# Artemis-Nano.net
KiCad netlist of a schematic drawn in EAGLE
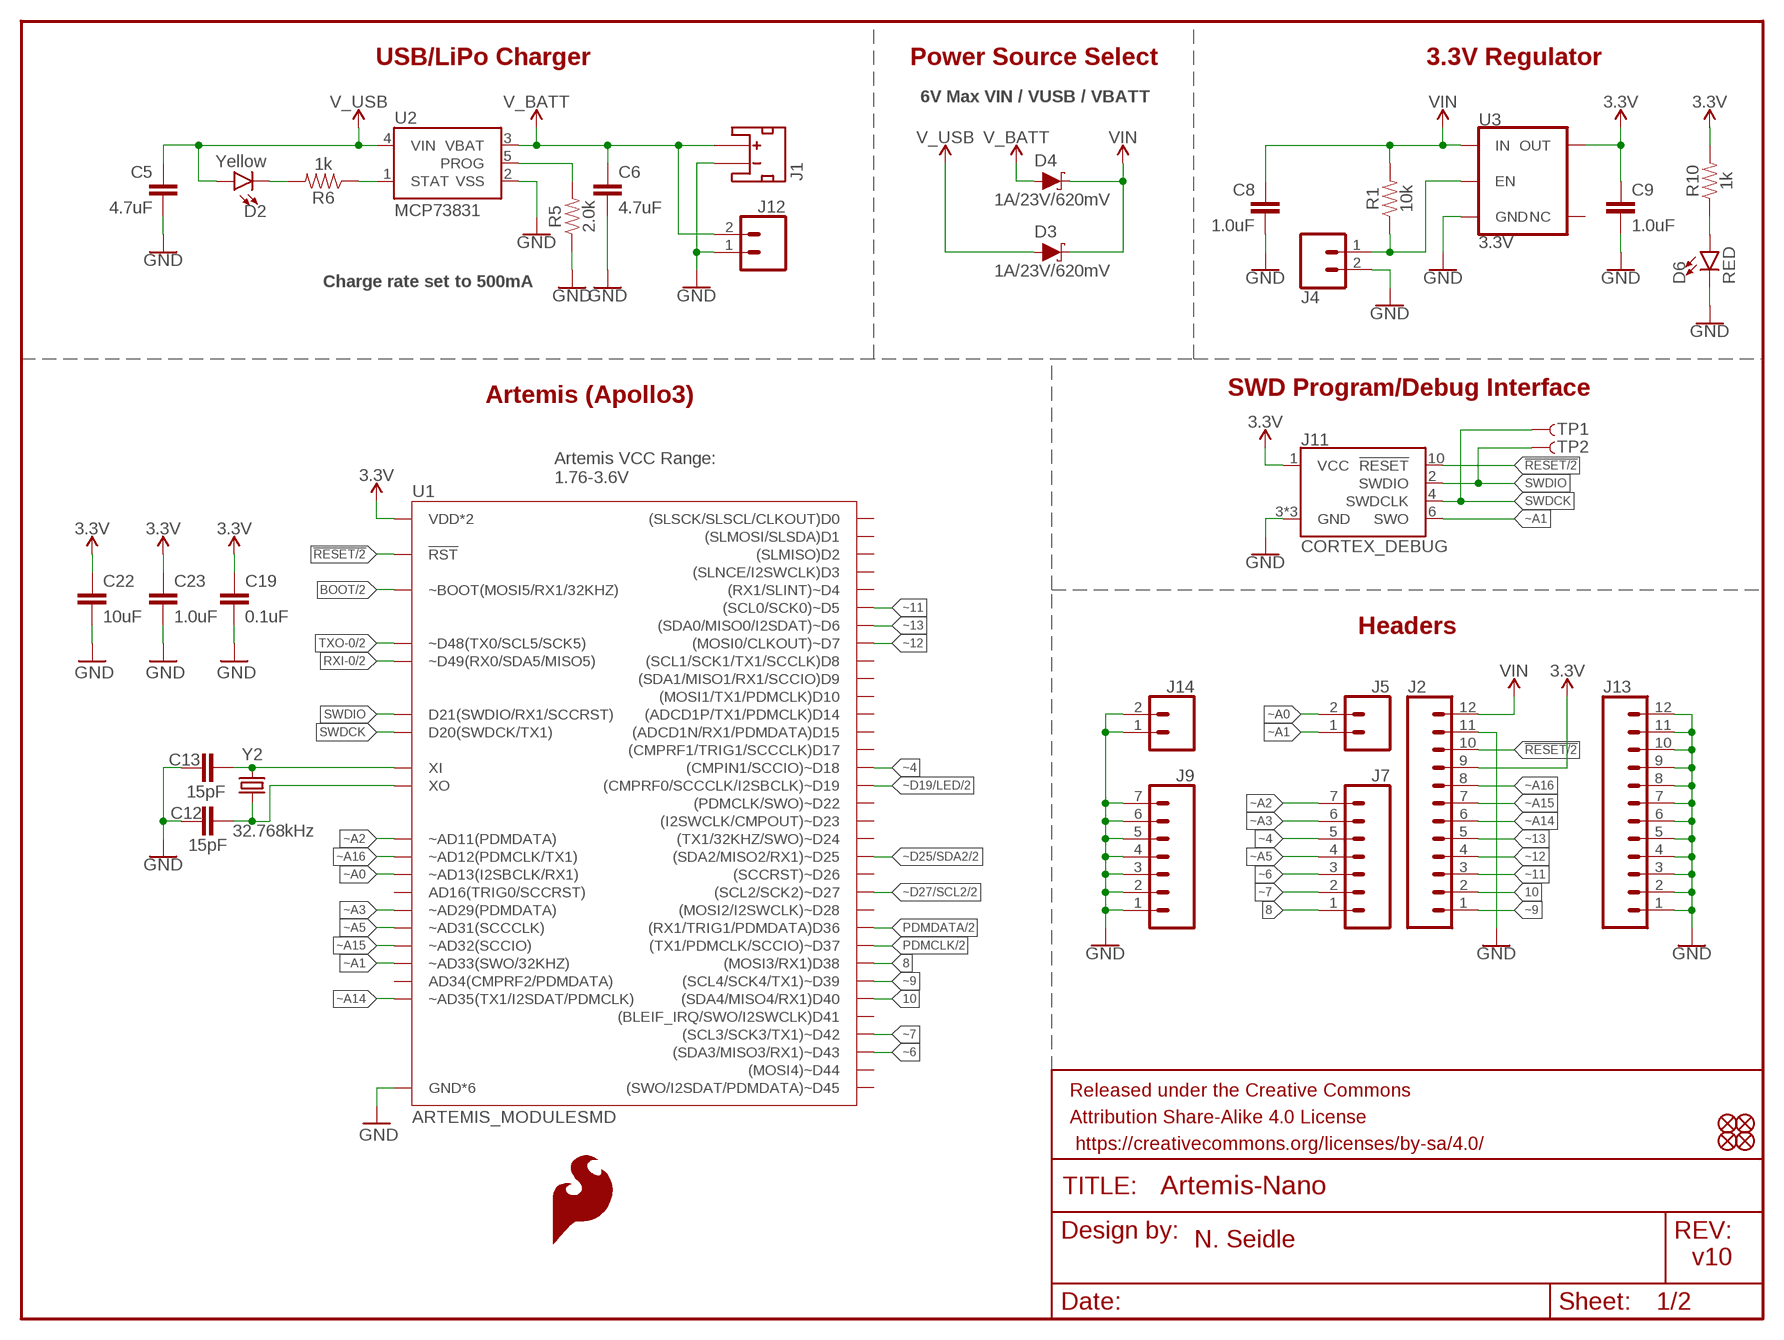
[diagram p0: schematic, sheet 1]
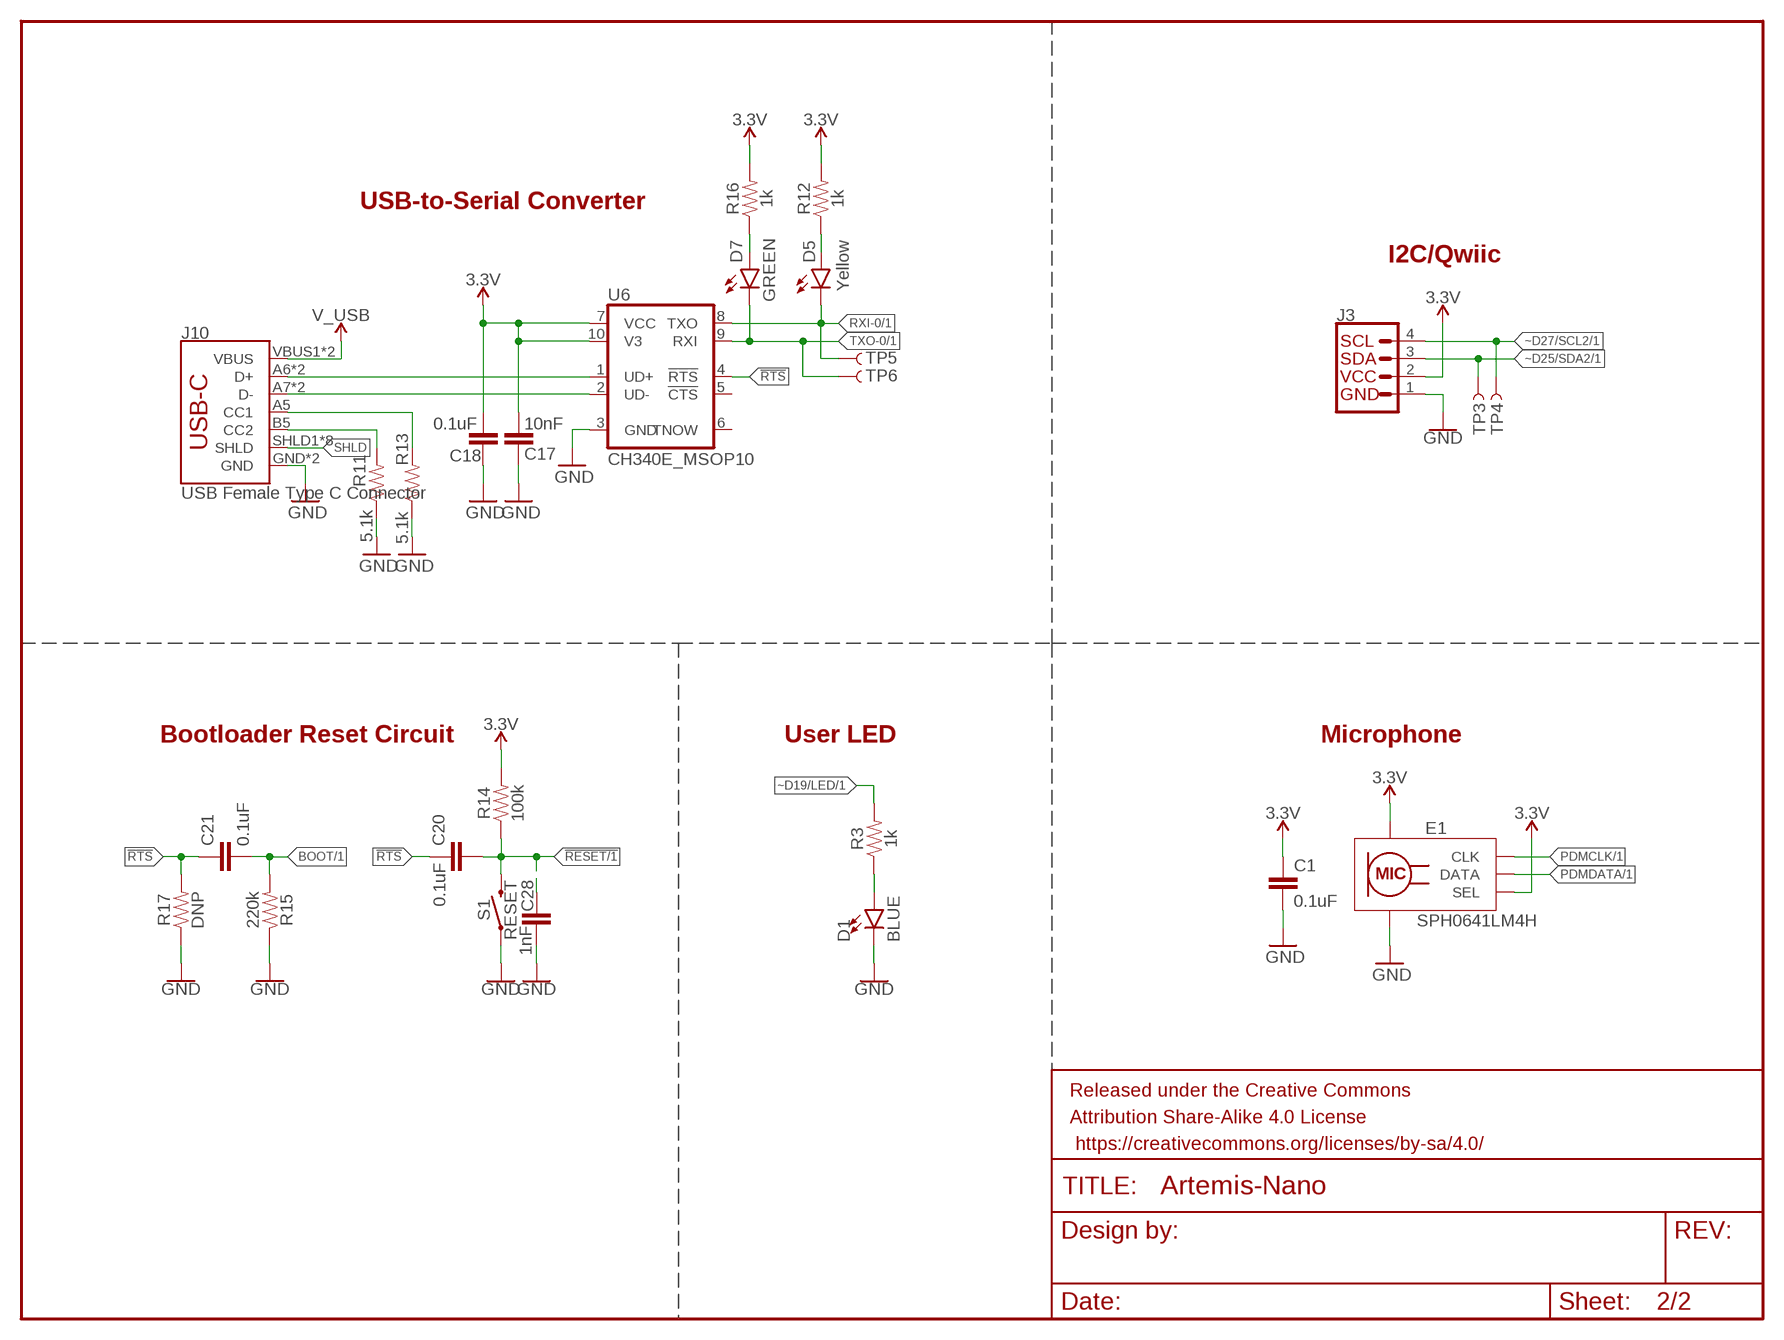
[diagram p1: schematic, sheet 2]

(export (version "E")
  (design (tool "Eeschema 10.0.6"))
  (components
    (comp (ref "C5")
      (value "4.7uF")
      (footprint "eagle-import:0603")
      (libsource (lib "eagle-import") (part "4.7UF-0603-6.3V-(10%)"))
    )
    (comp (ref "C6")
      (value "4.7uF")
      (footprint "eagle-import:0603")
      (libsource (lib "eagle-import") (part "4.7UF-0603-6.3V-(10%)"))
    )
    (comp (ref "C8")
      (value "1.0uF")
      (footprint "eagle-import:0402-TIGHT")
      (libsource (lib "eagle-import") (part "1.0UF-0402T-16V-10%"))
    )
    (comp (ref "C9")
      (value "1.0uF")
      (footprint "eagle-import:0402-TIGHT")
      (libsource (lib "eagle-import") (part "1.0UF-0402T-16V-10%"))
    )
    (comp (ref "C12")
      (value "15pF")
      (footprint "eagle-import:0603")
      (libsource (lib "eagle-import") (part "15PF-0603-50V-5%"))
    )
    (comp (ref "C13")
      (value "15pF")
      (footprint "eagle-import:0603")
      (libsource (lib "eagle-import") (part "15PF-0603-50V-5%"))
    )
    (comp (ref "C19")
      (value "0.1uF")
      (footprint "eagle-import:0402-TIGHT")
      (libsource (lib "eagle-import") (part "0.1UF-0402T-16V-10%"))
    )
    (comp (ref "C22")
      (value "10uF")
      (footprint "eagle-import:0603")
      (libsource (lib "eagle-import") (part "10UF-0603-6.3V-20%"))
    )
    (comp (ref "C23")
      (value "1.0uF")
      (footprint "eagle-import:0402-TIGHT")
      (libsource (lib "eagle-import") (part "1.0UF-0402T-16V-10%"))
    )
    (comp (ref "D2")
      (value "Yellow")
      (footprint "eagle-import:LED-0603")
      (libsource (lib "eagle-import") (part "LED-YELLOW0603"))
    )
    (comp (ref "D3")
      (value "1A/23V/620mV")
      (footprint "eagle-import:SOD-323")
      (libsource (lib "eagle-import") (part "DIODE-SCHOTTKY-BAT20J"))
    )
    (comp (ref "D4")
      (value "1A/23V/620mV")
      (footprint "eagle-import:SOD-323")
      (libsource (lib "eagle-import") (part "DIODE-SCHOTTKY-BAT20J"))
    )
    (comp (ref "D6")
      (value "RED")
      (footprint "eagle-import:LED-0603")
      (libsource (lib "eagle-import") (part "LED-RED0603"))
    )
    (comp (ref "FD1")
      (value "FIDUCIALUFIDUCIAL")
      (footprint "eagle-import:FIDUCIAL-MICRO")
      (libsource (lib "eagle-import") (part "FIDUCIALUFIDUCIAL"))
    )
    (comp (ref "FD2")
      (value "FIDUCIALUFIDUCIAL")
      (footprint "eagle-import:FIDUCIAL-MICRO")
      (libsource (lib "eagle-import") (part "FIDUCIALUFIDUCIAL"))
    )
    (comp (ref "FD3")
      (value "FIDUCIALUFIDUCIAL")
      (footprint "eagle-import:FIDUCIAL-MICRO")
      (libsource (lib "eagle-import") (part "FIDUCIALUFIDUCIAL"))
    )
    (comp (ref "FD4")
      (value "FIDUCIALUFIDUCIAL")
      (footprint "eagle-import:FIDUCIAL-MICRO")
      (libsource (lib "eagle-import") (part "FIDUCIALUFIDUCIAL"))
    )
    (comp (ref "FRAME1")
      (value "FRAME-LETTER")
      (footprint "eagle-import:CREATIVE_COMMONS")
      (libsource (lib "eagle-import") (part "FRAME-LETTER"))
    )
    (comp (ref "J1")
      (value "JST_2MM_MALE")
      (footprint "eagle-import:JST-2-SMD")
      (libsource (lib "eagle-import") (part "JST_2MM_MALE"))
    )
    (comp (ref "J2")
      (value "CONN_12NO_SILK")
      (footprint "eagle-import:1X12_NO_SILK")
      (libsource (lib "eagle-import") (part "CONN_12NO_SILK"))
    )
    (comp (ref "J4")
      (value "CONN_021X02_NO_SILK")
      (footprint "eagle-import:1X02_NO_SILK")
      (libsource (lib "eagle-import") (part "CONN_021X02_NO_SILK"))
    )
    (comp (ref "J5")
      (value "CONN_021X02_NO_SILK")
      (footprint "eagle-import:1X02_NO_SILK")
      (libsource (lib "eagle-import") (part "CONN_021X02_NO_SILK"))
    )
    (comp (ref "J7")
      (value "CONN_07NO_SILK")
      (footprint "eagle-import:1X07_NO_SILK")
      (libsource (lib "eagle-import") (part "CONN_07NO_SILK"))
    )
    (comp (ref "J9")
      (value "CONN_07NO_SILK")
      (footprint "eagle-import:1X07_NO_SILK")
      (libsource (lib "eagle-import") (part "CONN_07NO_SILK"))
    )
    (comp (ref "J11")
      (value "CORTEX_DEBUG")
      (footprint "eagle-import:2X5-PTH-1.27MM-NO_SILK")
      (libsource (lib "eagle-import") (part "CORTEX_DEBUG_MINIMUM_PTH_NS"))
    )
    (comp (ref "J12")
      (value "CONN_021X02_NO_SILK")
      (footprint "eagle-import:1X02_NO_SILK")
      (libsource (lib "eagle-import") (part "CONN_021X02_NO_SILK"))
    )
    (comp (ref "J13")
      (value "CONN_12NO_SILK")
      (footprint "eagle-import:1X12_NO_SILK")
      (libsource (lib "eagle-import") (part "CONN_12NO_SILK"))
    )
    (comp (ref "J14")
      (value "CONN_021X02_NO_SILK")
      (footprint "eagle-import:1X02_NO_SILK")
      (libsource (lib "eagle-import") (part "CONN_021X02_NO_SILK"))
    )
    (comp (ref "LOGO1")
      (value "SFE_LOGO_FLAME.1_INCH")
      (footprint "eagle-import:SFE_LOGO_FLAME_.1")
      (libsource (lib "eagle-import") (part "SFE_LOGO_FLAME.1_INCH"))
    )
    (comp (ref "LOGO4")
      (value "SFE_LOGO_FLAME.1_INCH")
      (footprint "eagle-import:SFE_LOGO_FLAME_.1")
      (libsource (lib "eagle-import") (part "SFE_LOGO_FLAME.1_INCH"))
    )
    (comp (ref "R1")
      (value "10k")
      (footprint "eagle-import:0603")
      (libsource (lib "eagle-import") (part "10KOHM-0603-1/10W-1%"))
    )
    (comp (ref "R5")
      (value "2.0k")
      (footprint "eagle-import:0603")
      (libsource (lib "eagle-import") (part "2.0KOHM-0603-1/10W-5%"))
    )
    (comp (ref "R6")
      (value "1k")
      (footprint "eagle-import:0603")
      (libsource (lib "eagle-import") (part "1KOHM-0603-1/10W-1%"))
    )
    (comp (ref "R10")
      (value "1k")
      (footprint "eagle-import:0603")
      (libsource (lib "eagle-import") (part "1KOHM-0603-1/10W-1%"))
    )
    (comp (ref "TP1")
      (value "TEST-POINT3X5")
      (footprint "eagle-import:PAD.03X.05")
      (libsource (lib "eagle-import") (part "TEST-POINT3X5"))
    )
    (comp (ref "TP2")
      (value "TEST-POINT3X5")
      (footprint "eagle-import:PAD.03X.05")
      (libsource (lib "eagle-import") (part "TEST-POINT3X5"))
    )
    (comp (ref "U1")
      (value "ARTEMIS_MODULESMD")
      (footprint "eagle-import:ARTEMIS_FP")
      (libsource (lib "eagle-import") (part "ARTEMIS_MODULESMD"))
    )
    (comp (ref "U2")
      (value "MCP73831")
      (footprint "eagle-import:SOT23-5")
      (libsource (lib "eagle-import") (part "MCP73831"))
    )
    (comp (ref "U3")
      (value "3.3V")
      (footprint "eagle-import:SOT23-5")
      (libsource (lib "eagle-import") (part "V_REG_AP2112K-3.3V"))
    )
    (comp (ref "Y2")
      (value "32.768kHz")
      (footprint "eagle-import:CRYSTAL-SMD-3.2X1.5MM")
      (libsource (lib "eagle-import") (part "CRYSTAL-32.768KHZSMD-3.2X1.5"))
    )
    (comp (ref "C1")
      (value "0.1uF")
      (footprint "eagle-import:0402-TIGHT")
      (libsource (lib "eagle-import") (part "0.1UF-0402T-16V-10%"))
    )
    (comp (ref "C17")
      (value "10nF")
      (footprint "eagle-import:0603")
      (libsource (lib "eagle-import") (part "10NF-0603-50V-10%"))
    )
    (comp (ref "C18")
      (value "0.1uF")
      (footprint "eagle-import:0603")
      (libsource (lib "eagle-import") (part "0.1UF-0603-25V-(+80/-20%)"))
    )
    (comp (ref "C20")
      (value "0.1uF")
      (footprint "eagle-import:0603")
      (libsource (lib "eagle-import") (part "0.1UF-0603-25V-5%"))
    )
    (comp (ref "C21")
      (value "0.1uF")
      (footprint "eagle-import:0603")
      (libsource (lib "eagle-import") (part "0.1UF-0603-25V-5%"))
    )
    (comp (ref "C28")
      (value "1nF")
      (footprint "eagle-import:0603")
      (libsource (lib "eagle-import") (part "1.0NF/1000PF-0603-50V-10%"))
    )
    (comp (ref "D1")
      (value "BLUE")
      (footprint "eagle-import:LED-0603")
      (libsource (lib "eagle-import") (part "LED-BLUE0603"))
    )
    (comp (ref "D5")
      (value "Yellow")
      (footprint "eagle-import:LED-0603")
      (libsource (lib "eagle-import") (part "LED-YELLOW0603"))
    )
    (comp (ref "D7")
      (value "GREEN")
      (footprint "eagle-import:LED-0603")
      (libsource (lib "eagle-import") (part "LED-GREEN0603"))
    )
    (comp (ref "E1")
      (value "SPH0641LM4H")
      (footprint "eagle-import:SPH0641LM4H-1_MICROPHONE")
      (libsource (lib "eagle-import") (part "SPH0641LM4H-1_MICROPHONE"))
    )
    (comp (ref "FRAME2")
      (value "FRAME-LETTERNO_PACKAGE")
      (footprint "eagle-import:DUMMY")
      (fields (field (name "DESIGNER") "Nobody"))
      (libsource (lib "eagle-import") (part "FRAME-LETTERNO_PACKAGE"))
    )
    (comp (ref "J3")
      (value "QWIIC_CONNECTORJS-1MM")
      (footprint "eagle-import:JST04_1MM_RA")
      (libsource (lib "eagle-import") (part "QWIIC_CONNECTORJS-1MM"))
    )
    (comp (ref "J10")
      (value "USB Female Type C Connector")
      (footprint "eagle-import:USB-C-16P-4LAYER-ISOLATED")
      (libsource (lib "eagle-import") (part "USB_C4-LAYER-ISOLATED"))
    )
    (comp (ref "R3")
      (value "1k")
      (footprint "eagle-import:0603")
      (libsource (lib "eagle-import") (part "1KOHM-0603-1/10W-1%"))
    )
    (comp (ref "R11")
      (value "5.1k")
      (footprint "eagle-import:0603")
      (libsource (lib "eagle-import") (part "5.1KOHM5.1KOHM-0603-1/10W-1%"))
    )
    (comp (ref "R12")
      (value "1k")
      (footprint "eagle-import:0603")
      (libsource (lib "eagle-import") (part "1KOHM-0603-1/10W-1%"))
    )
    (comp (ref "R13")
      (value "5.1k")
      (footprint "eagle-import:0603")
      (libsource (lib "eagle-import") (part "5.1KOHM5.1KOHM-0603-1/10W-1%"))
    )
    (comp (ref "R14")
      (value "100k")
      (footprint "eagle-import:0603")
      (libsource (lib "eagle-import") (part "100KOHM-0603-1/10W-1%"))
    )
    (comp (ref "R15")
      (value "220k")
      (footprint "eagle-import:0603")
      (libsource (lib "eagle-import") (part "220KOHM-0603-1/10W-1%"))
    )
    (comp (ref "R16")
      (value "1k")
      (footprint "eagle-import:0603")
      (libsource (lib "eagle-import") (part "1KOHM-0603-1/10W-1%"))
    )
    (comp (ref "R17")
      (value "DNP")
      (footprint "eagle-import:0603")
      (libsource (lib "eagle-import") (part "RESISTOR0603"))
    )
    (comp (ref "S1")
      (value "RESET")
      (footprint "eagle-import:TACTILE_SWITCH_SMD_4.6X2.8MM")
      (libsource (lib "eagle-import") (part "MOMENTARY-SWITCH-SPST-SMD-4.6X2.8MM"))
    )
    (comp (ref "TP3")
      (value "TEST-POINT3X5")
      (footprint "eagle-import:PAD.03X.05")
      (libsource (lib "eagle-import") (part "TEST-POINT3X5"))
    )
    (comp (ref "TP4")
      (value "TEST-POINT3X5")
      (footprint "eagle-import:PAD.03X.05")
      (libsource (lib "eagle-import") (part "TEST-POINT3X5"))
    )
    (comp (ref "TP5")
      (value "TEST-POINT3X5")
      (footprint "eagle-import:PAD.03X.05")
      (libsource (lib "eagle-import") (part "TEST-POINT3X5"))
    )
    (comp (ref "TP6")
      (value "TEST-POINT3X5")
      (footprint "eagle-import:PAD.03X.05")
      (libsource (lib "eagle-import") (part "TEST-POINT3X5"))
    )
    (comp (ref "U6")
      (value "CH340E_MSOP10")
      (footprint "eagle-import:MSOP10")
      (libsource (lib "eagle-import") (part "CH340E_MSOP10"))
    )
  )
  (nets
    (net (code "1") (name "3.3V") (class "Default")
      (node (ref "C1") (pin "1") (pinfunction "1_1") (pintype "passive"))
      (node (ref "C17") (pin "1") (pinfunction "1_1") (pintype "passive"))
      (node (ref "C18") (pin "1") (pinfunction "1_1") (pintype "passive"))
      (node (ref "C19") (pin "2") (pinfunction "2_2") (pintype "passive"))
      (node (ref "C22") (pin "1") (pinfunction "1_1") (pintype "passive"))
      (node (ref "C23") (pin "1") (pinfunction "1_1") (pintype "passive"))
      (node (ref "C9") (pin "1") (pinfunction "1_1") (pintype "passive"))
      (node (ref "E1") (pin "2") (pinfunction "SEL_2") (pintype "input"))
      (node (ref "E1") (pin "5") (pinfunction "VDD_5") (pintype "power_in"))
      (node (ref "J11") (pin "1") (pinfunction "VCC_1") (pintype "bidirectional"))
      (node (ref "J2") (pin "9") (pinfunction "9_9") (pintype "passive"))
      (node (ref "J3") (pin "2") (pinfunction "2_2") (pintype "power_in"))
      (node (ref "R10") (pin "2") (pinfunction "2_2") (pintype "passive"))
      (node (ref "R12") (pin "2") (pinfunction "2_2") (pintype "passive"))
      (node (ref "R14") (pin "2") (pinfunction "2_2") (pintype "passive"))
      (node (ref "R16") (pin "2") (pinfunction "2_2") (pintype "passive"))
      (node (ref "U1") (pin "VDD@36") (pinfunction "VDD*2_VDD@36") (pintype "bidirectional"))
      (node (ref "U1") (pin "VDD@37") (pinfunction "VDD*2_VDD@37") (pintype "bidirectional"))
      (node (ref "U3") (pin "5") (pinfunction "OUT_5") (pintype "passive"))
      (node (ref "U6") (pin "10") (pinfunction "V3_10") (pintype "bidirectional"))
      (node (ref "U6") (pin "7") (pinfunction "VCC_7") (pintype "bidirectional"))
    )
    (net (code "2") (name "8") (class "Default")
      (node (ref "J7") (pin "1") (pinfunction "1_1") (pintype "passive"))
      (node (ref "U1") (pin "D38") (pinfunction "(MOSI3/RX1)D38_D38") (pintype "bidirectional"))
    )
    (net (code "3") (name "10") (class "Default")
      (node (ref "J2") (pin "2") (pinfunction "2_2") (pintype "passive"))
      (node (ref "U1") (pin "D40") (pinfunction "(SDA4/MISO4/RX1)D40_D40") (pintype "bidirectional"))
    )
    (net (code "4") (name "BOOT") (class "Default")
      (node (ref "C21") (pin "2") (pinfunction "2_2") (pintype "passive"))
      (node (ref "R15") (pin "2") (pinfunction "2_2") (pintype "passive"))
      (node (ref "U1") (pin "BOOT") (pinfunction "~{BOOT(MOSI5/RX1/32KHZ})_BOOT") (pintype "bidirectional"))
    )
    (net (code "5") (name "GND") (class "Default")
      (node (ref "C1") (pin "2") (pinfunction "2_2") (pintype "passive"))
      (node (ref "C12") (pin "1") (pinfunction "1_1") (pintype "passive"))
      (node (ref "C13") (pin "1") (pinfunction "1_1") (pintype "passive"))
      (node (ref "C17") (pin "2") (pinfunction "2_2") (pintype "passive"))
      (node (ref "C18") (pin "2") (pinfunction "2_2") (pintype "passive"))
      (node (ref "C19") (pin "1") (pinfunction "1_1") (pintype "passive"))
      (node (ref "C22") (pin "2") (pinfunction "2_2") (pintype "passive"))
      (node (ref "C23") (pin "2") (pinfunction "2_2") (pintype "passive"))
      (node (ref "C28") (pin "2") (pinfunction "2_2") (pintype "passive"))
      (node (ref "C5") (pin "2") (pinfunction "2_2") (pintype "passive"))
      (node (ref "C6") (pin "2") (pinfunction "2_2") (pintype "passive"))
      (node (ref "C8") (pin "2") (pinfunction "2_2") (pintype "passive"))
      (node (ref "C9") (pin "2") (pinfunction "2_2") (pintype "passive"))
      (node (ref "D1") (pin "C") (pinfunction "C_C") (pintype "passive"))
      (node (ref "D6") (pin "C") (pinfunction "C_C") (pintype "passive"))
      (node (ref "E1") (pin "3") (pinfunction "GND_3") (pintype "power_in"))
      (node (ref "E1") (pin "6") (pinfunction "GND_6") (pintype "power_in"))
      (node (ref "E1") (pin "7") (pinfunction "GND_7") (pintype "power_in"))
      (node (ref "E1") (pin "8") (pinfunction "GND_8") (pintype "power_in"))
      (node (ref "J1") (pin "1") (pinfunction "-_1") (pintype "bidirectional"))
      (node (ref "J10") (pin "GND") (pinfunction "GND_GND") (pintype "bidirectional"))
      (node (ref "J10") (pin "GND2") (pinfunction "GND_GND2") (pintype "bidirectional"))
      (node (ref "J11") (pin "3") (pinfunction "GND_3") (pintype "bidirectional"))
      (node (ref "J11") (pin "5") (pinfunction "GND_5") (pintype "bidirectional"))
      (node (ref "J11") (pin "9") (pinfunction "GND_9") (pintype "bidirectional"))
      (node (ref "J12") (pin "1") (pinfunction "1_1") (pintype "passive"))
      (node (ref "J13") (pin "1") (pinfunction "1_1") (pintype "passive"))
      (node (ref "J13") (pin "10") (pinfunction "10_10") (pintype "passive"))
      (node (ref "J13") (pin "11") (pinfunction "11_11") (pintype "passive"))
      (node (ref "J13") (pin "12") (pinfunction "12_12") (pintype "passive"))
      (node (ref "J13") (pin "2") (pinfunction "2_2") (pintype "passive"))
      (node (ref "J13") (pin "3") (pinfunction "3_3") (pintype "passive"))
      (node (ref "J13") (pin "4") (pinfunction "4_4") (pintype "passive"))
      (node (ref "J13") (pin "5") (pinfunction "5_5") (pintype "passive"))
      (node (ref "J13") (pin "6") (pinfunction "6_6") (pintype "passive"))
      (node (ref "J13") (pin "7") (pinfunction "7_7") (pintype "passive"))
      (node (ref "J13") (pin "8") (pinfunction "8_8") (pintype "passive"))
      (node (ref "J13") (pin "9") (pinfunction "9_9") (pintype "passive"))
      (node (ref "J14") (pin "1") (pinfunction "1_1") (pintype "passive"))
      (node (ref "J14") (pin "2") (pinfunction "2_2") (pintype "passive"))
      (node (ref "J2") (pin "11") (pinfunction "11_11") (pintype "passive"))
      (node (ref "J3") (pin "1") (pinfunction "1_1") (pintype "power_in"))
      (node (ref "J4") (pin "2") (pinfunction "2_2") (pintype "passive"))
      (node (ref "J9") (pin "1") (pinfunction "1_1") (pintype "passive"))
      (node (ref "J9") (pin "2") (pinfunction "2_2") (pintype "passive"))
      (node (ref "J9") (pin "3") (pinfunction "3_3") (pintype "passive"))
      (node (ref "J9") (pin "4") (pinfunction "4_4") (pintype "passive"))
      (node (ref "J9") (pin "5") (pinfunction "5_5") (pintype "passive"))
      (node (ref "J9") (pin "6") (pinfunction "6_6") (pintype "passive"))
      (node (ref "J9") (pin "7") (pinfunction "7_7") (pintype "passive"))
      (node (ref "R11") (pin "1") (pinfunction "1_1") (pintype "passive"))
      (node (ref "R13") (pin "1") (pinfunction "1_1") (pintype "passive"))
      (node (ref "R15") (pin "1") (pinfunction "1_1") (pintype "passive"))
      (node (ref "R17") (pin "1") (pinfunction "1_1") (pintype "passive"))
      (node (ref "R5") (pin "1") (pinfunction "1_1") (pintype "passive"))
      (node (ref "S1") (pin "1") (pinfunction "1_1") (pintype "passive"))
      (node (ref "S1") (pin "2") (pinfunction "1_2") (pintype "passive"))
      (node (ref "U1") (pin "GND@1") (pinfunction "GND*6_GND@1") (pintype "bidirectional"))
      (node (ref "U1") (pin "GND@22") (pinfunction "GND*6_GND@22") (pintype "bidirectional"))
      (node (ref "U1") (pin "GND@38") (pinfunction "GND*6_GND@38") (pintype "bidirectional"))
      (node (ref "U1") (pin "GND@39") (pinfunction "GND*6_GND@39") (pintype "bidirectional"))
      (node (ref "U1") (pin "GND@47") (pinfunction "GND*6_GND@47") (pintype "bidirectional"))
      (node (ref "U1") (pin "GND@59") (pinfunction "GND*6_GND@59") (pintype "bidirectional"))
      (node (ref "U2") (pin "2") (pinfunction "VSS_2") (pintype "power_in"))
      (node (ref "U3") (pin "2") (pinfunction "GND_2") (pintype "input"))
      (node (ref "U6") (pin "3") (pinfunction "GND_3") (pintype "bidirectional"))
    )
    (net (code "6") (name "Net-(D1-PadA)") (class "Default")
      (node (ref "D1") (pin "A") (pinfunction "A_A") (pintype "passive"))
      (node (ref "R3") (pin "1") (pinfunction "1_1") (pintype "passive"))
    )
    (net (code "7") (name "Net-(D2-PadC)") (class "Default")
      (node (ref "D2") (pin "C") (pinfunction "C_C") (pintype "passive"))
      (node (ref "R6") (pin "2") (pinfunction "2_2") (pintype "passive"))
    )
    (net (code "8") (name "Net-(D5-PadA)") (class "Default")
      (node (ref "D5") (pin "A") (pinfunction "A_A") (pintype "passive"))
      (node (ref "R12") (pin "1") (pinfunction "1_1") (pintype "passive"))
    )
    (net (code "9") (name "Net-(D6-PadA)") (class "Default")
      (node (ref "D6") (pin "A") (pinfunction "A_A") (pintype "passive"))
      (node (ref "R10") (pin "1") (pinfunction "1_1") (pintype "passive"))
    )
    (net (code "10") (name "Net-(D7-PadA)") (class "Default")
      (node (ref "D7") (pin "A") (pinfunction "A_A") (pintype "passive"))
      (node (ref "R16") (pin "1") (pinfunction "1_1") (pintype "passive"))
    )
    (net (code "11") (name "Net-(J10-CC1)") (class "Default")
      (node (ref "J10") (pin "A5") (pinfunction "CC1_A5") (pintype "bidirectional"))
      (node (ref "R13") (pin "2") (pinfunction "2_2") (pintype "passive"))
    )
    (net (code "12") (name "Net-(J10-CC2)") (class "Default")
      (node (ref "J10") (pin "B5") (pinfunction "CC2_B5") (pintype "bidirectional"))
      (node (ref "R11") (pin "2") (pinfunction "2_2") (pintype "passive"))
    )
    (net (code "13") (name "Net-(U2-PROG)") (class "Default")
      (node (ref "R5") (pin "2") (pinfunction "2_2") (pintype "passive"))
      (node (ref "U2") (pin "5") (pinfunction "PROG_5") (pintype "input"))
    )
    (net (code "14") (name "Net-(U2-STAT)") (class "Default")
      (node (ref "R6") (pin "1") (pinfunction "1_1") (pintype "passive"))
      (node (ref "U2") (pin "1") (pinfunction "STAT_1") (pintype "output"))
    )
    (net (code "15") (name "Net-(U3-EN)") (class "Default")
      (node (ref "J4") (pin "1") (pinfunction "1_1") (pintype "passive"))
      (node (ref "R1") (pin "1") (pinfunction "1_1") (pintype "passive"))
      (node (ref "U3") (pin "3") (pinfunction "EN_3") (pintype "input"))
    )
    (net (code "16") (name "Net-(U6-UD+)") (class "Default")
      (node (ref "J10") (pin "A6") (pinfunction "D+_A6") (pintype "bidirectional"))
      (node (ref "J10") (pin "B6") (pinfunction "D+_B6") (pintype "bidirectional"))
      (node (ref "U6") (pin "1") (pinfunction "UD+_1") (pintype "bidirectional"))
    )
    (net (code "17") (name "Net-(U6-UD-)") (class "Default")
      (node (ref "J10") (pin "A7") (pinfunction "D-_A7") (pintype "bidirectional"))
      (node (ref "J10") (pin "B7") (pinfunction "D-_B7") (pintype "bidirectional"))
      (node (ref "U6") (pin "2") (pinfunction "UD-_2") (pintype "bidirectional"))
    )
    (net (code "18") (name "Net-(Y2-1)") (class "Default")
      (node (ref "C13") (pin "2") (pinfunction "2_2") (pintype "passive"))
      (node (ref "U1") (pin "XI") (pinfunction "XI_XI") (pintype "bidirectional"))
      (node (ref "Y2") (pin "P$1") (pinfunction "1_P$1") (pintype "passive"))
    )
    (net (code "19") (name "Net-(Y2-2)") (class "Default")
      (node (ref "C12") (pin "2") (pinfunction "2_2") (pintype "passive"))
      (node (ref "U1") (pin "XO") (pinfunction "XO_XO") (pintype "bidirectional"))
      (node (ref "Y2") (pin "P$2") (pinfunction "2_P$2") (pintype "passive"))
    )
    (net (code "20") (name "PDMCLK") (class "Default")
      (node (ref "E1") (pin "4") (pinfunction "CLK_4") (pintype "input"))
      (node (ref "U1") (pin "~D37") (pinfunction "(TX1/PDMCLK/SCCIO)~{D37}_~D37") (pintype "bidirectional"))
    )
    (net (code "21") (name "PDMDATA") (class "Default")
      (node (ref "E1") (pin "1") (pinfunction "DATA_1") (pintype "output"))
      (node (ref "U1") (pin "D36") (pinfunction "(RX1/TRIG1/PDMDATA)D36_D36") (pintype "bidirectional"))
    )
    (net (code "22") (name "RXI-0") (class "Default")
      (node (ref "D5") (pin "C") (pinfunction "C_C") (pintype "passive"))
      (node (ref "TP5") (pin "P$1") (pinfunction "1_P$1") (pintype "bidirectional"))
      (node (ref "U1") (pin "RXI-0") (pinfunction "~{D49(RX0/SDA5/MISO5})_RXI-0") (pintype "bidirectional"))
      (node (ref "U6") (pin "8") (pinfunction "TXO_8") (pintype "bidirectional"))
    )
    (net (code "23") (name "SHLD") (class "Default")
      (node (ref "J10") (pin "SHLD1") (pinfunction "SHLD_SHLD1") (pintype "bidirectional"))
      (node (ref "J10") (pin "SHLD2") (pinfunction "SHLD_SHLD2") (pintype "bidirectional"))
      (node (ref "J10") (pin "SHLD3") (pinfunction "SHLD_SHLD3") (pintype "bidirectional"))
      (node (ref "J10") (pin "SHLD4") (pinfunction "SHLD_SHLD4") (pintype "bidirectional"))
      (node (ref "J10") (pin "SHLD5") (pinfunction "SHLD_SHLD5") (pintype "bidirectional"))
      (node (ref "J10") (pin "SHLD6") (pinfunction "SHLD_SHLD6") (pintype "bidirectional"))
      (node (ref "J10") (pin "SHLD7") (pinfunction "SHLD_SHLD7") (pintype "bidirectional"))
      (node (ref "J10") (pin "SHLD8") (pinfunction "SHLD_SHLD8") (pintype "bidirectional"))
    )
    (net (code "24") (name "SWDCK") (class "Default")
      (node (ref "J11") (pin "4") (pinfunction "SWDCLK_4") (pintype "bidirectional"))
      (node (ref "TP1") (pin "P$1") (pinfunction "1_P$1") (pintype "bidirectional"))
      (node (ref "U1") (pin "SWDCK") (pinfunction "D20(SWDCK/TX1)_SWDCK") (pintype "bidirectional"))
    )
    (net (code "25") (name "SWDIO") (class "Default")
      (node (ref "J11") (pin "2") (pinfunction "SWDIO_2") (pintype "bidirectional"))
      (node (ref "TP2") (pin "P$1") (pinfunction "1_P$1") (pintype "bidirectional"))
      (node (ref "U1") (pin "SWDIO") (pinfunction "D21(SWDIO/RX1/SCCRST)_SWDIO") (pintype "bidirectional"))
    )
    (net (code "26") (name "TXO-0") (class "Default")
      (node (ref "D7") (pin "C") (pinfunction "C_C") (pintype "passive"))
      (node (ref "TP6") (pin "P$1") (pinfunction "1_P$1") (pintype "bidirectional"))
      (node (ref "U1") (pin "TXO-0") (pinfunction "~{D48(TX0/SCL5/SCK5})_TXO-0") (pintype "bidirectional"))
      (node (ref "U6") (pin "9") (pinfunction "RXI_9") (pintype "bidirectional"))
    )
    (net (code "27") (name "VIN") (class "Default")
      (node (ref "C8") (pin "1") (pinfunction "1_1") (pintype "passive"))
      (node (ref "D3") (pin "C") (pinfunction "C_C") (pintype "passive"))
      (node (ref "D4") (pin "C") (pinfunction "C_C") (pintype "passive"))
      (node (ref "J2") (pin "12") (pinfunction "12_12") (pintype "passive"))
      (node (ref "R1") (pin "2") (pinfunction "2_2") (pintype "passive"))
      (node (ref "U3") (pin "1") (pinfunction "IN_1") (pintype "input"))
    )
    (net (code "28") (name "V_BATT") (class "Default")
      (node (ref "C6") (pin "1") (pinfunction "1_1") (pintype "passive"))
      (node (ref "D4") (pin "A") (pinfunction "A_A") (pintype "passive"))
      (node (ref "J1") (pin "2") (pinfunction "+_2") (pintype "bidirectional"))
      (node (ref "J12") (pin "2") (pinfunction "2_2") (pintype "passive"))
      (node (ref "U2") (pin "3") (pinfunction "VBAT_3") (pintype "power_in"))
    )
    (net (code "29") (name "V_USB") (class "Default")
      (node (ref "C5") (pin "1") (pinfunction "1_1") (pintype "passive"))
      (node (ref "D2") (pin "A") (pinfunction "A_A") (pintype "passive"))
      (node (ref "D3") (pin "A") (pinfunction "A_A") (pintype "passive"))
      (node (ref "J10") (pin "VBUS1") (pinfunction "VBUS_VBUS1") (pintype "bidirectional"))
      (node (ref "J10") (pin "VBUS2") (pinfunction "VBUS_VBUS2") (pintype "bidirectional"))
      (node (ref "U2") (pin "4") (pinfunction "VIN_4") (pintype "power_in"))
    )
    (net (code "30") (name "unconnected-(J1-PAD1-PadNC1)") (class "Default")
      (node (ref "J1") (pin "NC1") (pinfunction "PAD1_NC1") (pintype "bidirectional"))
    )
    (net (code "31") (name "unconnected-(J1-PAD2-PadNC2)") (class "Default")
      (node (ref "J1") (pin "NC2") (pinfunction "PAD2_NC2") (pintype "bidirectional"))
    )
    (net (code "32") (name "unconnected-(U1-(ADCD1N{slash}RX1{slash}PDMDATA)D15-PadD15)") (class "Default")
      (node (ref "U1") (pin "D15") (pinfunction "(ADCD1N/RX1/PDMDATA)D15_D15") (pintype "bidirectional"))
    )
    (net (code "33") (name "unconnected-(U1-(ADCD1P{slash}TX1{slash}PDMCLK)D14-PadD14)") (class "Default")
      (node (ref "U1") (pin "D14") (pinfunction "(ADCD1P/TX1/PDMCLK)D14_D14") (pintype "bidirectional"))
    )
    (net (code "34") (name "unconnected-(U1-(BLEIF_IRQ{slash}SWO{slash}I2SWCLK)D41-PadD41)") (class "Default")
      (node (ref "U1") (pin "D41") (pinfunction "(BLEIF_IRQ/SWO/I2SWCLK)D41_D41") (pintype "bidirectional"))
    )
    (net (code "35") (name "unconnected-(U1-(CMPRF1{slash}TRIG1{slash}SCCCLK)D17-PadD17)") (class "Default")
      (node (ref "U1") (pin "D17") (pinfunction "(CMPRF1/TRIG1/SCCCLK)D17_D17") (pintype "bidirectional"))
    )
    (net (code "36") (name "unconnected-(U1-(I2SWCLK{slash}CMPOUT)~{D23}-Pad~D23)") (class "Default")
      (node (ref "U1") (pin "~D23") (pinfunction "(I2SWCLK/CMPOUT)~{D23}_~D23") (pintype "bidirectional"))
    )
    (net (code "37") (name "unconnected-(U1-(MOSI1{slash}TX1{slash}PDMCLK)D10-PadD10)") (class "Default")
      (node (ref "U1") (pin "D10") (pinfunction "(MOSI1/TX1/PDMCLK)D10_D10") (pintype "bidirectional"))
    )
    (net (code "38") (name "unconnected-(U1-(MOSI2{slash}I2SWCLK)~{D28}-Pad~D28)") (class "Default")
      (node (ref "U1") (pin "~D28") (pinfunction "(MOSI2/I2SWCLK)~{D28}_~D28") (pintype "bidirectional"))
    )
    (net (code "39") (name "unconnected-(U1-(MOSI4)~{D44}-Pad~D44)") (class "Default")
      (node (ref "U1") (pin "~D44") (pinfunction "(MOSI4)~{D44}_~D44") (pintype "bidirectional"))
    )
    (net (code "40") (name "unconnected-(U1-(PDMCLK{slash}SWO)~{D22}-Pad~D22)") (class "Default")
      (node (ref "U1") (pin "~D22") (pinfunction "(PDMCLK/SWO)~{D22}_~D22") (pintype "bidirectional"))
    )
    (net (code "41") (name "unconnected-(U1-(RX1{slash}SLINT)~{D4}-Pad~D4)") (class "Default")
      (node (ref "U1") (pin "~D4") (pinfunction "(RX1/SLINT)~{D4}_~D4") (pintype "bidirectional"))
    )
    (net (code "42") (name "unconnected-(U1-(SCCRST)~{D26}-Pad~D26)") (class "Default")
      (node (ref "U1") (pin "~D26") (pinfunction "(SCCRST)~{D26}_~D26") (pintype "bidirectional"))
    )
    (net (code "43") (name "unconnected-(U1-(SCL1{slash}SCK1{slash}TX1{slash}SCCLK)D8-PadD8)") (class "Default")
      (node (ref "U1") (pin "D8") (pinfunction "(SCL1/SCK1/TX1/SCCLK)D8_D8") (pintype "bidirectional"))
    )
    (net (code "44") (name "unconnected-(U1-(SDA1{slash}MISO1{slash}RX1{slash}SCCIO)D9-PadD9)") (class "Default")
      (node (ref "U1") (pin "D9") (pinfunction "(SDA1/MISO1/RX1/SCCIO)D9_D9") (pintype "bidirectional"))
    )
    (net (code "45") (name "unconnected-(U1-(SLMISO)D2-PadD2)") (class "Default")
      (node (ref "U1") (pin "D2") (pinfunction "(SLMISO)D2_D2") (pintype "bidirectional"))
    )
    (net (code "46") (name "unconnected-(U1-(SLMOSI{slash}SLSDA)D1-PadD1)") (class "Default")
      (node (ref "U1") (pin "D1") (pinfunction "(SLMOSI/SLSDA)D1_D1") (pintype "bidirectional"))
    )
    (net (code "47") (name "unconnected-(U1-(SLNCE{slash}I2SWCLK)D3-PadD3)") (class "Default")
      (node (ref "U1") (pin "D3") (pinfunction "(SLNCE/I2SWCLK)D3_D3") (pintype "bidirectional"))
    )
    (net (code "48") (name "unconnected-(U1-(SLSCK{slash}SLSCL{slash}CLKOUT)D0-PadD0)") (class "Default")
      (node (ref "U1") (pin "D0") (pinfunction "(SLSCK/SLSCL/CLKOUT)D0_D0") (pintype "bidirectional"))
    )
    (net (code "49") (name "unconnected-(U1-(SWO{slash}I2SDAT{slash}PDMDATA)~{D45}-Pad~D45)") (class "Default")
      (node (ref "U1") (pin "~D45") (pinfunction "(SWO/I2SDAT/PDMDATA)~{D45}_~D45") (pintype "bidirectional"))
    )
    (net (code "50") (name "unconnected-(U1-(TX1{slash}32KHZ{slash}SWO)~{D24}-Pad~D24)") (class "Default")
      (node (ref "U1") (pin "~D24") (pinfunction "(TX1/32KHZ/SWO)~{D24}_~D24") (pintype "bidirectional"))
    )
    (net (code "51") (name "unconnected-(U1-AD16(TRIG0{slash}SCCRST)-PadAD16)") (class "Default")
      (node (ref "U1") (pin "AD16") (pinfunction "AD16(TRIG0/SCCRST)_AD16") (pintype "bidirectional"))
    )
    (net (code "52") (name "unconnected-(U1-AD34(CMPRF2{slash}PDMDATA)-PadAD34)") (class "Default")
      (node (ref "U1") (pin "AD34") (pinfunction "AD34(CMPRF2/PDMDATA)_AD34") (pintype "bidirectional"))
    )
    (net (code "53") (name "unconnected-(U3-NC-Pad4)") (class "Default")
      (node (ref "U3") (pin "4") (pinfunction "NC_4") (pintype "no_connect"))
    )
    (net (code "54") (name "unconnected-(U6-TNOW-Pad6)") (class "Default")
      (node (ref "U6") (pin "6") (pinfunction "TNOW_6") (pintype "bidirectional"))
    )
    (net (code "55") (name "unconnected-(U6-~{CTS}-Pad5)") (class "Default")
      (node (ref "U6") (pin "5") (pinfunction "~{CTS}_5") (pintype "bidirectional"))
    )
    (net (code "56") (name "~{4}") (class "Default")
      (node (ref "J7") (pin "5") (pinfunction "5_5") (pintype "passive"))
      (node (ref "U1") (pin "~D18") (pinfunction "(CMPIN1/SCCIO)~{D18}_~D18") (pintype "bidirectional"))
    )
    (net (code "57") (name "~{6}") (class "Default")
      (node (ref "J7") (pin "3") (pinfunction "3_3") (pintype "passive"))
      (node (ref "U1") (pin "~D43") (pinfunction "(SDA3/MISO3/RX1)~{D43}_~D43") (pintype "bidirectional"))
    )
    (net (code "58") (name "~{7}") (class "Default")
      (node (ref "J7") (pin "2") (pinfunction "2_2") (pintype "passive"))
      (node (ref "U1") (pin "~D42") (pinfunction "(SCL3/SCK3/TX1)~{D42}_~D42") (pintype "bidirectional"))
    )
    (net (code "59") (name "~{9}") (class "Default")
      (node (ref "J2") (pin "1") (pinfunction "1_1") (pintype "passive"))
      (node (ref "U1") (pin "~D39") (pinfunction "(SCL4/SCK4/TX1)~{D39}_~D39") (pintype "bidirectional"))
    )
    (net (code "60") (name "~{11}") (class "Default")
      (node (ref "J2") (pin "3") (pinfunction "3_3") (pintype "passive"))
      (node (ref "U1") (pin "~D5") (pinfunction "(SCL0/SCK0)~{D5}_~D5") (pintype "bidirectional"))
    )
    (net (code "61") (name "~{12}") (class "Default")
      (node (ref "J2") (pin "4") (pinfunction "4_4") (pintype "passive"))
      (node (ref "U1") (pin "D7") (pinfunction "(MOSI0/CLKOUT)~{D7}_D7") (pintype "bidirectional"))
    )
    (net (code "62") (name "~{13}") (class "Default")
      (node (ref "J2") (pin "5") (pinfunction "5_5") (pintype "passive"))
      (node (ref "U1") (pin "~D6") (pinfunction "(SDA0/MISO0/I2SDAT)~{D6}_~D6") (pintype "bidirectional"))
    )
    (net (code "63") (name "~{A0}") (class "Default")
      (node (ref "J5") (pin "2") (pinfunction "2_2") (pintype "passive"))
      (node (ref "U1") (pin "~AD13") (pinfunction "~{AD13(I2SBCLK/RX1})_~AD13") (pintype "bidirectional"))
    )
    (net (code "64") (name "~{A1}") (class "Default")
      (node (ref "J11") (pin "6") (pinfunction "SWO_6") (pintype "bidirectional"))
      (node (ref "J5") (pin "1") (pinfunction "1_1") (pintype "passive"))
      (node (ref "U1") (pin "~AD33/SWO") (pinfunction "~{AD33(SWO/32KHZ})_~AD33/SWO") (pintype "bidirectional"))
    )
    (net (code "65") (name "~{A2}") (class "Default")
      (node (ref "J7") (pin "7") (pinfunction "7_7") (pintype "passive"))
      (node (ref "U1") (pin "~AD11") (pinfunction "~{AD11(PDMDATA})_~AD11") (pintype "bidirectional"))
    )
    (net (code "66") (name "~{A3}") (class "Default")
      (node (ref "J7") (pin "6") (pinfunction "6_6") (pintype "passive"))
      (node (ref "U1") (pin "~AD29") (pinfunction "~{AD29(PDMDATA})_~AD29") (pintype "bidirectional"))
    )
    (net (code "67") (name "~{A5}") (class "Default")
      (node (ref "J7") (pin "4") (pinfunction "4_4") (pintype "passive"))
      (node (ref "U1") (pin "~AD31") (pinfunction "~{AD31(SCCCLK})_~AD31") (pintype "bidirectional"))
    )
    (net (code "68") (name "~{A14}") (class "Default")
      (node (ref "J2") (pin "6") (pinfunction "6_6") (pintype "passive"))
      (node (ref "U1") (pin "~AD35") (pinfunction "~{AD35(TX1/I2SDAT/PDMCLK})_~AD35") (pintype "bidirectional"))
    )
    (net (code "69") (name "~{A15}") (class "Default")
      (node (ref "J2") (pin "7") (pinfunction "7_7") (pintype "passive"))
      (node (ref "U1") (pin "~AD32") (pinfunction "~{AD32(SCCIO})_~AD32") (pintype "bidirectional"))
    )
    (net (code "70") (name "~{A16}") (class "Default")
      (node (ref "J2") (pin "8") (pinfunction "8_8") (pintype "passive"))
      (node (ref "U1") (pin "~AD12") (pinfunction "~{AD12(PDMCLK/TX1})_~AD12") (pintype "bidirectional"))
    )
    (net (code "71") (name "~{D19{slash}LED}") (class "Default")
      (node (ref "R3") (pin "2") (pinfunction "2_2") (pintype "passive"))
      (node (ref "U1") (pin "~D19") (pinfunction "(CMPRF0/SCCCLK/I2SBCLK)~{D19}_~D19") (pintype "bidirectional"))
    )
    (net (code "72") (name "~{D25{slash}SDA2}") (class "Default")
      (node (ref "J3") (pin "3") (pinfunction "3_3") (pintype "passive"))
      (node (ref "TP3") (pin "P$1") (pinfunction "1_P$1") (pintype "bidirectional"))
      (node (ref "U1") (pin "~D25") (pinfunction "(SDA2/MISO2/RX1)~{D25}_~D25") (pintype "bidirectional"))
    )
    (net (code "73") (name "~{D27{slash}SCL2}") (class "Default")
      (node (ref "J3") (pin "4") (pinfunction "4_4") (pintype "passive"))
      (node (ref "TP4") (pin "P$1") (pinfunction "1_P$1") (pintype "bidirectional"))
      (node (ref "U1") (pin "~D27") (pinfunction "(SCL2/SCK2)~{D27}_~D27") (pintype "bidirectional"))
    )
    (net (code "74") (name "~{RESET}") (class "Default")
      (node (ref "C20") (pin "2") (pinfunction "2_2") (pintype "passive"))
      (node (ref "C28") (pin "1") (pinfunction "1_1") (pintype "passive"))
      (node (ref "J11") (pin "10") (pinfunction "~{RESET}_10") (pintype "bidirectional"))
      (node (ref "J2") (pin "10") (pinfunction "10_10") (pintype "passive"))
      (node (ref "R14") (pin "1") (pinfunction "1_1") (pintype "passive"))
      (node (ref "S1") (pin "3") (pinfunction "2_3") (pintype "passive"))
      (node (ref "S1") (pin "4") (pinfunction "2_4") (pintype "passive"))
      (node (ref "U1") (pin "~RST") (pinfunction "~{RST}_~RST") (pintype "bidirectional"))
    )
    (net (code "75") (name "~{RTS}") (class "Default")
      (node (ref "C20") (pin "1") (pinfunction "1_1") (pintype "passive"))
      (node (ref "C21") (pin "1") (pinfunction "1_1") (pintype "passive"))
      (node (ref "R17") (pin "2") (pinfunction "2_2") (pintype "passive"))
      (node (ref "U6") (pin "4") (pinfunction "~{RTS}_4") (pintype "bidirectional"))
    )
  )
)
